# 28Pins_Schematic.net
KiCad netlist of a schematic drawn in Altium Designer
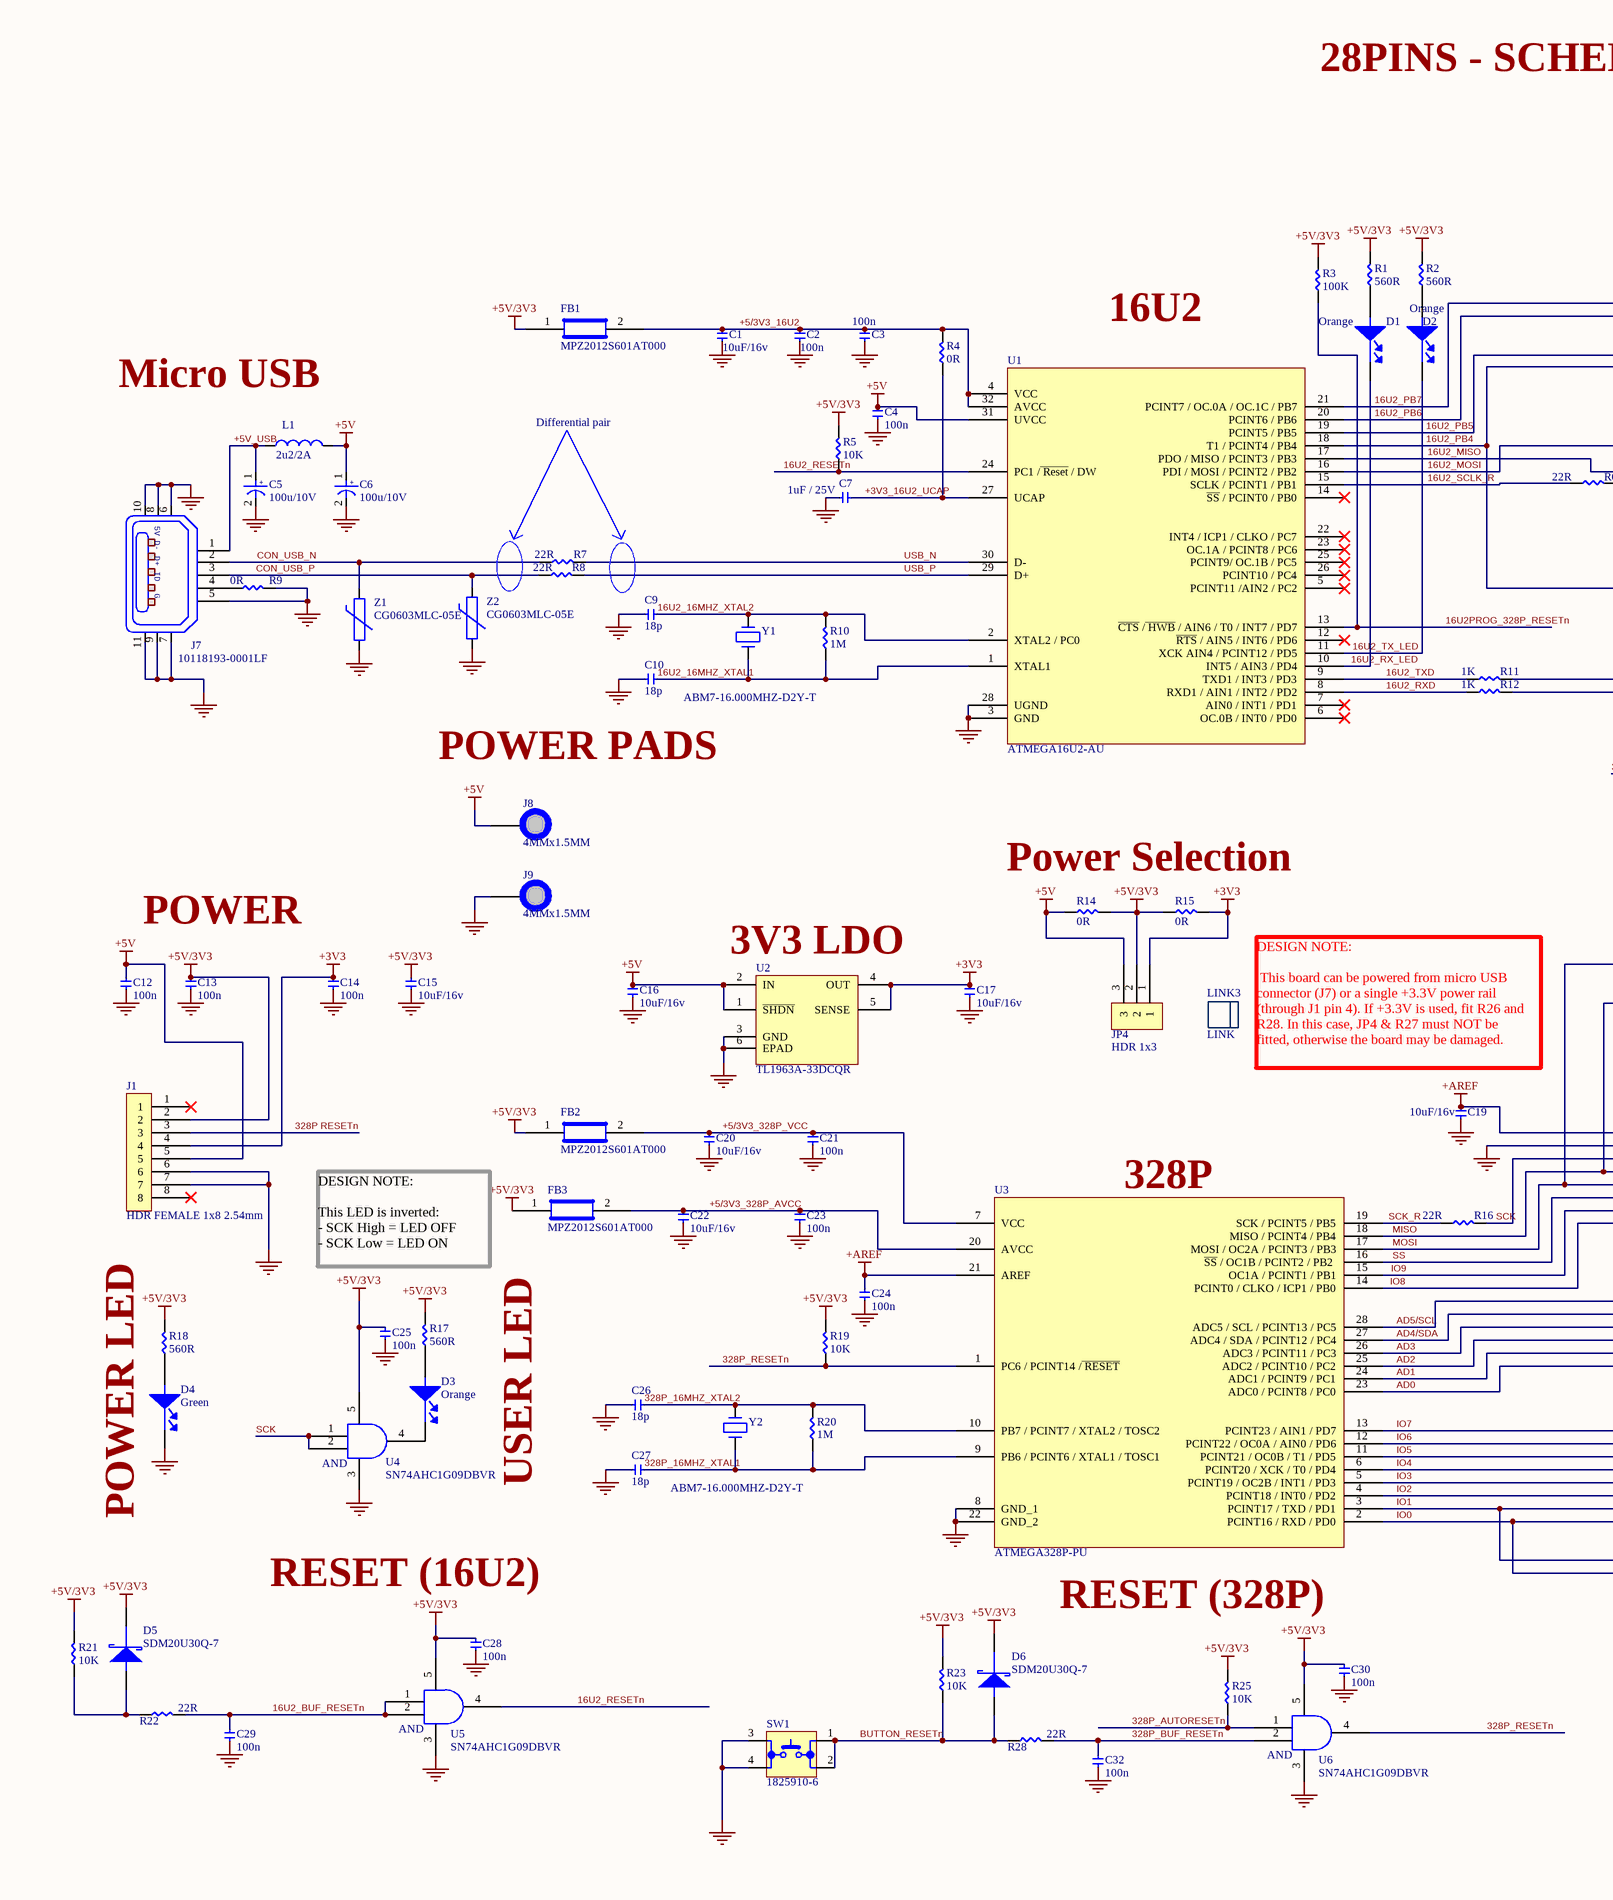
[diagram p0: 28Pins_Schematic.SchDoc, left]
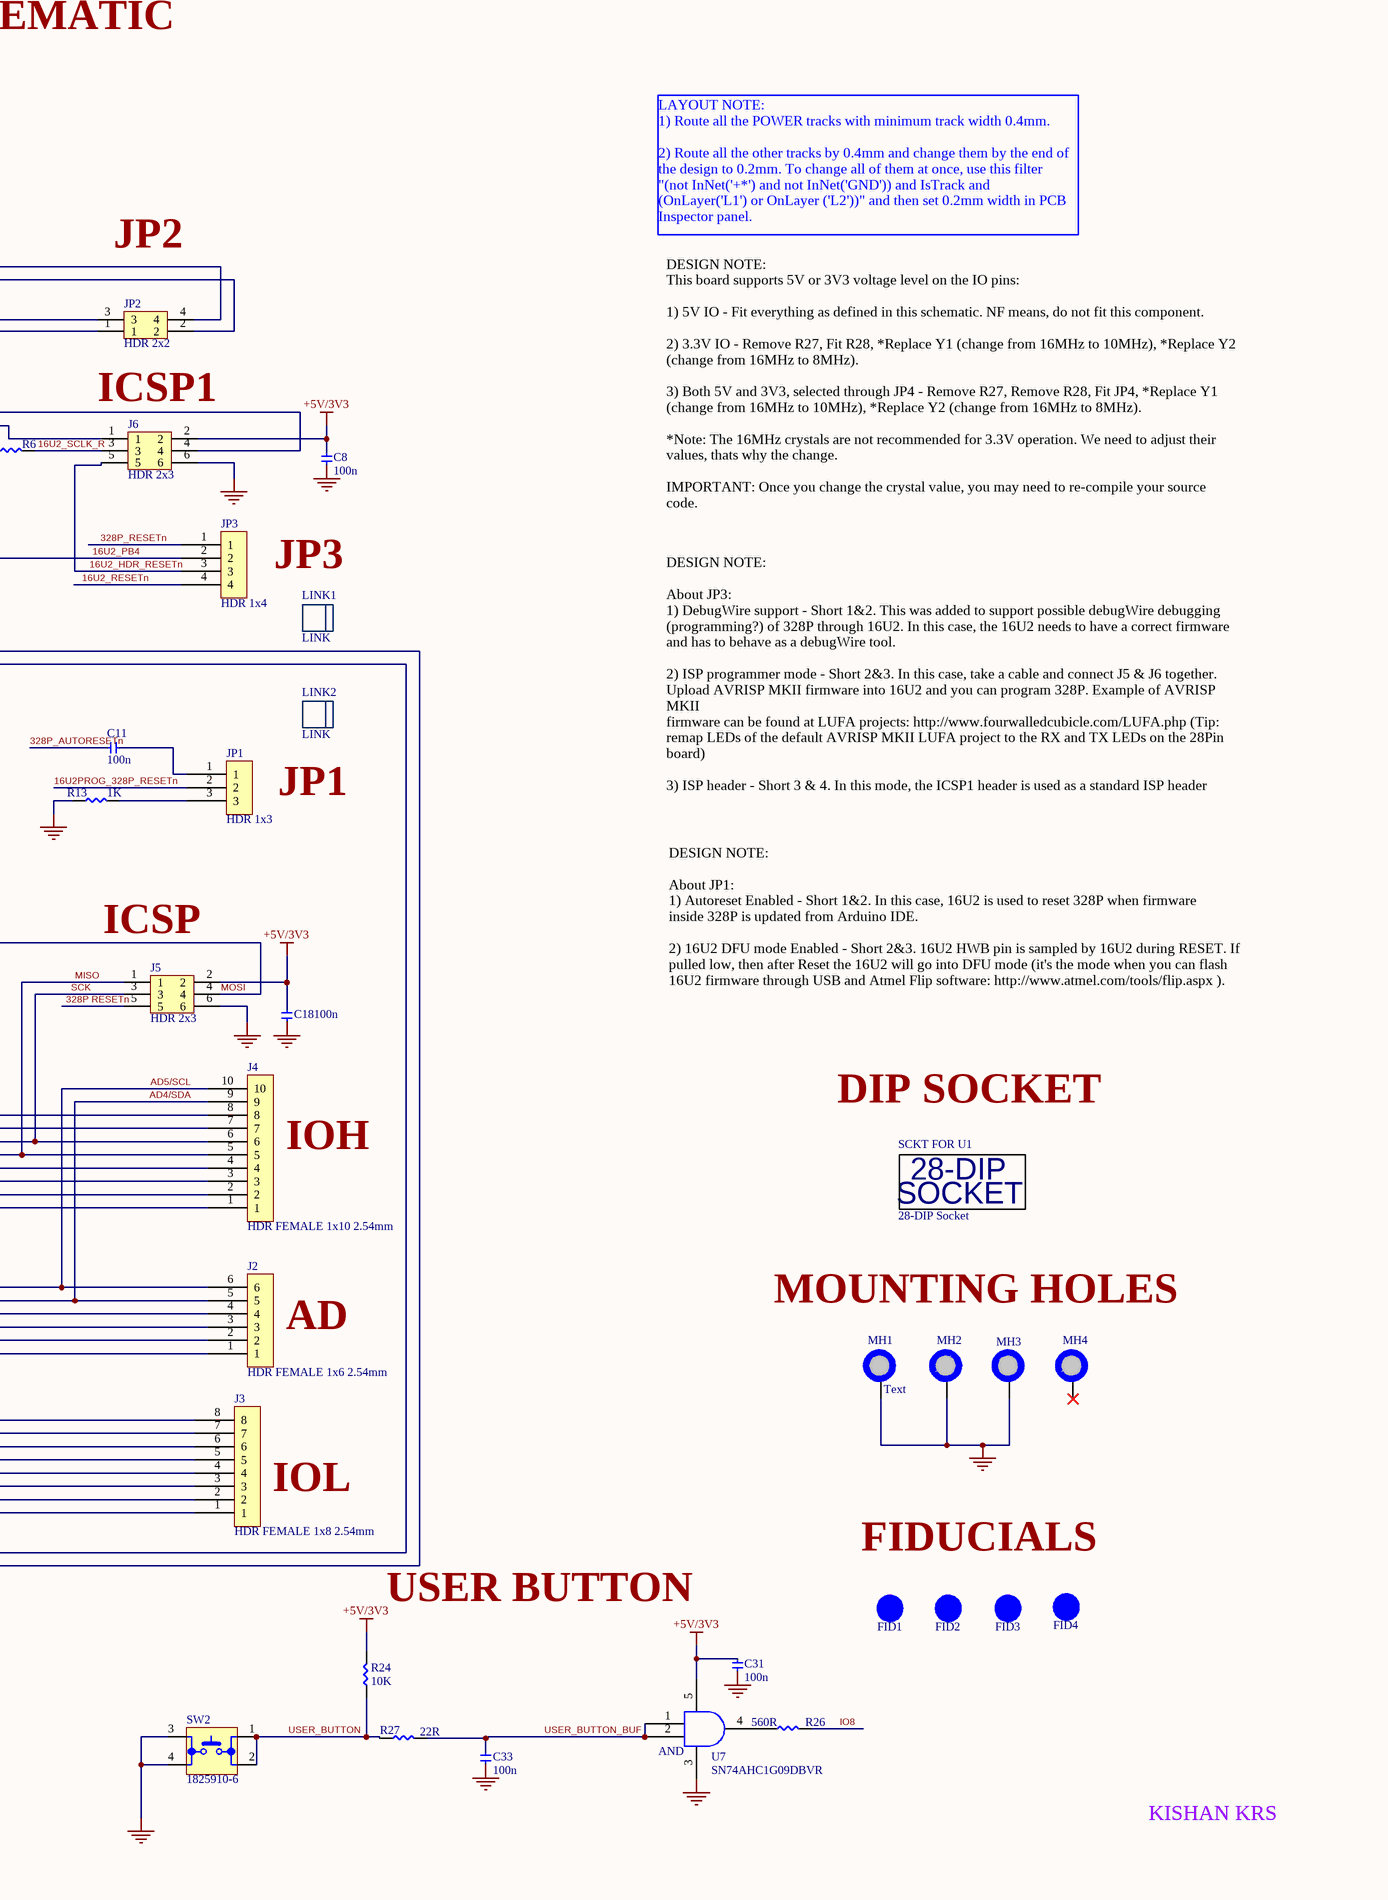
[diagram p1: 28Pins_Schematic.SchDoc, right]

(export (version "E")
  (design (tool "Eeschema 10.0.6"))
  (components
    (comp (ref "C1")
      (value "10uF/16v")
      (footprint "C0805")
      (fields
        (field (name "MANUFACTURER") "TDK")
        (field (name "MANUFACTURER PART NUMBER") "CGA4J1X5R1C106K125AC")
        (field (name "TOLERANCE") "10%")
      )
      (libsource (lib "28Pins_Project_V1I1") (part "CGA4J1X5R1C106K125AC"))
    )
    (comp (ref "C2")
      (value "100n")
      (footprint "C0805")
      (description "C Series 0805 0.1 uF 50 V ±10 % Tolerance X7R SMT Multilayer Ceramic Capacitor")
      (fields
        (field (name "MANUFACTURER") "TDK")
        (field (name "MANUFACTURER PART NUMBER") "C2012X7R1H104K085AA")
      )
      (libsource (lib "28Pins_Project_V1I1") (part "C2012X7R1H104K085AA"))
    )
    (comp (ref "C3")
      (value "100n")
      (footprint "C0805")
      (description "C Series 0805 0.1 uF 50 V ±10 % Tolerance X7R SMT Multilayer Ceramic Capacitor")
      (fields
        (field (name "MANUFACTURER") "TDK")
        (field (name "MANUFACTURER PART NUMBER") "C2012X7R1H104K085AA")
      )
      (libsource (lib "28Pins_Project_V1I1") (part "C2012X7R1H104K085AA"))
    )
    (comp (ref "C4")
      (value "100n")
      (footprint "C0805")
      (description "C Series 0805 0.1 uF 50 V ±10 % Tolerance X7R SMT Multilayer Ceramic Capacitor")
      (fields
        (field (name "MANUFACTURER") "TDK")
        (field (name "MANUFACTURER PART NUMBER") "C2012X7R1H104K085AA")
      )
      (libsource (lib "28Pins_Project_V1I1") (part "C2012X7R1H104K085AA"))
    )
    (comp (ref "C5")
      (value "100u/10V")
      (footprint "C_ALU_C_SIZE")
      (description "CAP ALUM 100UF 20% 10V SMD")
      (fields
        (field (name "MANUFACTURER") "Panasonic")
        (field (name "MANUFACTURER PART NUMBER") "EEE-1AA101WR")
      )
      (libsource (lib "28Pins_Project_V1I1") (part "EEE-1AA101WR"))
    )
    (comp (ref "C6")
      (value "100u/10V")
      (footprint "C_ALU_C_SIZE")
      (description "CAP ALUM 100UF 20% 10V SMD")
      (fields
        (field (name "MANUFACTURER") "Panasonic")
        (field (name "MANUFACTURER PART NUMBER") "EEE-1AA101WR")
      )
      (libsource (lib "28Pins_Project_V1I1") (part "EEE-1AA101WR"))
    )
    (comp (ref "C7")
      (value "1uF / 25V")
      (footprint "C0805")
      (fields
        (field (name "MANUFACTURER") "TDK")
        (field (name "MANUFACTURER PART NUMBER") "C2012X5R1E105K125AA")
        (field (name "TOLERANCE") "10%")
      )
      (libsource (lib "28Pins_Project_V1I1") (part "C2012X5R1E105K125AA"))
    )
    (comp (ref "C8")
      (value "100n")
      (footprint "C0805")
      (description "C Series 0805 0.1 uF 50 V ±10 % Tolerance X7R SMT Multilayer Ceramic Capacitor")
      (fields
        (field (name "MANUFACTURER") "TDK")
        (field (name "MANUFACTURER PART NUMBER") "C2012X7R1H104K085AA")
      )
      (libsource (lib "28Pins_Project_V1I1") (part "C2012X7R1H104K085AA"))
    )
    (comp (ref "C9")
      (value "18p")
      (footprint "C0805")
      (description "Cap Ceramic 18pF 50V C0G 5% SMD 0805 125C Paper T/R")
      (fields
        (field (name "MANUFACTURER") "KEMET")
        (field (name "MANUFACTURER PART NUMBER") "C0805C180J5GACTU")
      )
      (libsource (lib "28Pins_Project_V1I1") (part "C0805C180J5GACTU"))
    )
    (comp (ref "C10")
      (value "18p")
      (footprint "C0805")
      (description "Cap Ceramic 18pF 50V C0G 5% SMD 0805 125C Paper T/R")
      (fields
        (field (name "MANUFACTURER") "KEMET")
        (field (name "MANUFACTURER PART NUMBER") "C0805C180J5GACTU")
      )
      (libsource (lib "28Pins_Project_V1I1") (part "C0805C180J5GACTU"))
    )
    (comp (ref "C11")
      (value "100n")
      (footprint "C0805")
      (description "C Series 0805 0.1 uF 50 V ±10 % Tolerance X7R SMT Multilayer Ceramic Capacitor")
      (fields
        (field (name "MANUFACTURER") "TDK")
        (field (name "MANUFACTURER PART NUMBER") "C2012X7R1H104K085AA")
      )
      (libsource (lib "28Pins_Project_V1I1") (part "C2012X7R1H104K085AA"))
    )
    (comp (ref "C12")
      (value "100n")
      (footprint "C0805")
      (description "C Series 0805 0.1 uF 50 V ±10 % Tolerance X7R SMT Multilayer Ceramic Capacitor")
      (fields
        (field (name "MANUFACTURER") "TDK")
        (field (name "MANUFACTURER PART NUMBER") "C2012X7R1H104K085AA")
      )
      (libsource (lib "28Pins_Project_V1I1") (part "C2012X7R1H104K085AA"))
    )
    (comp (ref "C13")
      (value "100n")
      (footprint "C0805")
      (description "C Series 0805 0.1 uF 50 V ±10 % Tolerance X7R SMT Multilayer Ceramic Capacitor")
      (fields
        (field (name "MANUFACTURER") "TDK")
        (field (name "MANUFACTURER PART NUMBER") "C2012X7R1H104K085AA")
      )
      (libsource (lib "28Pins_Project_V1I1") (part "C2012X7R1H104K085AA"))
    )
    (comp (ref "C14")
      (value "100n")
      (footprint "C0805")
      (description "C Series 0805 0.1 uF 50 V ±10 % Tolerance X7R SMT Multilayer Ceramic Capacitor")
      (fields
        (field (name "MANUFACTURER") "TDK")
        (field (name "MANUFACTURER PART NUMBER") "C2012X7R1H104K085AA")
      )
      (libsource (lib "28Pins_Project_V1I1") (part "C2012X7R1H104K085AA"))
    )
    (comp (ref "C15")
      (value "10uF/16v")
      (footprint "C0805")
      (fields
        (field (name "MANUFACTURER") "TDK")
        (field (name "MANUFACTURER PART NUMBER") "CGA4J1X5R1C106K125AC")
        (field (name "TOLERANCE") "10%")
      )
      (libsource (lib "28Pins_Project_V1I1") (part "CGA4J1X5R1C106K125AC"))
    )
    (comp (ref "C16")
      (value "10uF/16v")
      (footprint "C0805")
      (fields
        (field (name "MANUFACTURER") "TDK")
        (field (name "MANUFACTURER PART NUMBER") "CGA4J1X5R1C106K125AC")
        (field (name "TOLERANCE") "10%")
      )
      (libsource (lib "28Pins_Project_V1I1") (part "CGA4J1X5R1C106K125AC"))
    )
    (comp (ref "C17")
      (value "10uF/16v")
      (footprint "C0805")
      (fields
        (field (name "MANUFACTURER") "TDK")
        (field (name "MANUFACTURER PART NUMBER") "CGA4J1X5R1C106K125AC")
        (field (name "TOLERANCE") "10%")
      )
      (libsource (lib "28Pins_Project_V1I1") (part "CGA4J1X5R1C106K125AC"))
    )
    (comp (ref "C18")
      (value "100n")
      (footprint "C0805")
      (description "C Series 0805 0.1 uF 50 V ±10 % Tolerance X7R SMT Multilayer Ceramic Capacitor")
      (fields
        (field (name "MANUFACTURER") "TDK")
        (field (name "MANUFACTURER PART NUMBER") "C2012X7R1H104K085AA")
      )
      (libsource (lib "28Pins_Project_V1I1") (part "C2012X7R1H104K085AA"))
    )
    (comp (ref "C19")
      (value "10uF/16v")
      (footprint "C0805")
      (fields
        (field (name "MANUFACTURER") "TDK")
        (field (name "MANUFACTURER PART NUMBER") "CGA4J1X5R1C106K125AC")
        (field (name "TOLERANCE") "10%")
      )
      (libsource (lib "28Pins_Project_V1I1") (part "CGA4J1X5R1C106K125AC"))
    )
    (comp (ref "C20")
      (value "10uF/16v")
      (footprint "C0805")
      (fields
        (field (name "MANUFACTURER") "TDK")
        (field (name "MANUFACTURER PART NUMBER") "CGA4J1X5R1C106K125AC")
        (field (name "TOLERANCE") "10%")
      )
      (libsource (lib "28Pins_Project_V1I1") (part "CGA4J1X5R1C106K125AC"))
    )
    (comp (ref "C21")
      (value "100n")
      (footprint "C0805")
      (description "C Series 0805 0.1 uF 50 V ±10 % Tolerance X7R SMT Multilayer Ceramic Capacitor")
      (fields
        (field (name "MANUFACTURER") "TDK")
        (field (name "MANUFACTURER PART NUMBER") "C2012X7R1H104K085AA")
      )
      (libsource (lib "28Pins_Project_V1I1") (part "C2012X7R1H104K085AA"))
    )
    (comp (ref "C22")
      (value "10uF/16v")
      (footprint "C0805")
      (fields
        (field (name "MANUFACTURER") "TDK")
        (field (name "MANUFACTURER PART NUMBER") "CGA4J1X5R1C106K125AC")
        (field (name "TOLERANCE") "10%")
      )
      (libsource (lib "28Pins_Project_V1I1") (part "CGA4J1X5R1C106K125AC"))
    )
    (comp (ref "C23")
      (value "100n")
      (footprint "C0805")
      (description "C Series 0805 0.1 uF 50 V ±10 % Tolerance X7R SMT Multilayer Ceramic Capacitor")
      (fields
        (field (name "MANUFACTURER") "TDK")
        (field (name "MANUFACTURER PART NUMBER") "C2012X7R1H104K085AA")
      )
      (libsource (lib "28Pins_Project_V1I1") (part "C2012X7R1H104K085AA"))
    )
    (comp (ref "C24")
      (value "100n")
      (footprint "C0805")
      (description "C Series 0805 0.1 uF 50 V ±10 % Tolerance X7R SMT Multilayer Ceramic Capacitor")
      (fields
        (field (name "MANUFACTURER") "TDK")
        (field (name "MANUFACTURER PART NUMBER") "C2012X7R1H104K085AA")
      )
      (libsource (lib "28Pins_Project_V1I1") (part "C2012X7R1H104K085AA"))
    )
    (comp (ref "C25")
      (value "100n")
      (footprint "C0805")
      (description "C Series 0805 0.1 uF 50 V ±10 % Tolerance X7R SMT Multilayer Ceramic Capacitor")
      (fields
        (field (name "MANUFACTURER") "TDK")
        (field (name "MANUFACTURER PART NUMBER") "C2012X7R1H104K085AA")
      )
      (libsource (lib "28Pins_Project_V1I1") (part "C2012X7R1H104K085AA"))
    )
    (comp (ref "C26")
      (value "18p")
      (footprint "C0805")
      (description "Cap Ceramic 18pF 50V C0G 5% SMD 0805 125C Paper T/R")
      (fields
        (field (name "MANUFACTURER") "KEMET")
        (field (name "MANUFACTURER PART NUMBER") "C0805C180J5GACTU")
      )
      (libsource (lib "28Pins_Project_V1I1") (part "C0805C180J5GACTU"))
    )
    (comp (ref "C27")
      (value "18p")
      (footprint "C0805")
      (description "Cap Ceramic 18pF 50V C0G 5% SMD 0805 125C Paper T/R")
      (fields
        (field (name "MANUFACTURER") "KEMET")
        (field (name "MANUFACTURER PART NUMBER") "C0805C180J5GACTU")
      )
      (libsource (lib "28Pins_Project_V1I1") (part "C0805C180J5GACTU"))
    )
    (comp (ref "C28")
      (value "100n")
      (footprint "C0805")
      (description "C Series 0805 0.1 uF 50 V ±10 % Tolerance X7R SMT Multilayer Ceramic Capacitor")
      (fields
        (field (name "MANUFACTURER") "TDK")
        (field (name "MANUFACTURER PART NUMBER") "C2012X7R1H104K085AA")
      )
      (libsource (lib "28Pins_Project_V1I1") (part "C2012X7R1H104K085AA"))
    )
    (comp (ref "C29")
      (value "100n")
      (footprint "C0805")
      (description "C Series 0805 0.1 uF 50 V ±10 % Tolerance X7R SMT Multilayer Ceramic Capacitor")
      (fields
        (field (name "MANUFACTURER") "TDK")
        (field (name "MANUFACTURER PART NUMBER") "C2012X7R1H104K085AA")
      )
      (libsource (lib "28Pins_Project_V1I1") (part "C2012X7R1H104K085AA"))
    )
    (comp (ref "C30")
      (value "100n")
      (footprint "C0805")
      (description "C Series 0805 0.1 uF 50 V ±10 % Tolerance X7R SMT Multilayer Ceramic Capacitor")
      (fields
        (field (name "MANUFACTURER") "TDK")
        (field (name "MANUFACTURER PART NUMBER") "C2012X7R1H104K085AA")
      )
      (libsource (lib "28Pins_Project_V1I1") (part "C2012X7R1H104K085AA"))
    )
    (comp (ref "C31")
      (value "100n")
      (footprint "C0805")
      (description "C Series 0805 0.1 uF 50 V ±10 % Tolerance X7R SMT Multilayer Ceramic Capacitor")
      (fields
        (field (name "MANUFACTURER") "TDK")
        (field (name "MANUFACTURER PART NUMBER") "C2012X7R1H104K085AA")
      )
      (libsource (lib "28Pins_Project_V1I1") (part "C2012X7R1H104K085AA"))
    )
    (comp (ref "C32")
      (value "100n")
      (footprint "C0805")
      (description "C Series 0805 0.1 uF 50 V ±10 % Tolerance X7R SMT Multilayer Ceramic Capacitor")
      (fields
        (field (name "MANUFACTURER") "TDK")
        (field (name "MANUFACTURER PART NUMBER") "C2012X7R1H104K085AA")
      )
      (libsource (lib "28Pins_Project_V1I1") (part "C2012X7R1H104K085AA"))
    )
    (comp (ref "C33")
      (value "100n")
      (footprint "C0805")
      (description "C Series 0805 0.1 uF 50 V ±10 % Tolerance X7R SMT Multilayer Ceramic Capacitor")
      (fields
        (field (name "MANUFACTURER") "TDK")
        (field (name "MANUFACTURER PART NUMBER") "C2012X7R1H104K085AA")
      )
      (libsource (lib "28Pins_Project_V1I1") (part "C2012X7R1H104K085AA"))
    )
    (comp (ref "D1")
      (value "Orange")
      (footprint "LED_0603")
      (description "Smartled Orange Lc")
      (fields
        (field (name "MANUFACTURER") "Osram Opto")
        (field (name "MANUFACTURER PART NUMBER") "LOL29K-H2K1-24-Z")
      )
      (libsource (lib "28Pins_Project_V1I1") (part "LOL29K-H2K1-24-Z"))
    )
    (comp (ref "D2")
      (value "Orange")
      (footprint "LED_0603")
      (description "Smartled Orange Lc")
      (fields
        (field (name "MANUFACTURER") "Osram Opto")
        (field (name "MANUFACTURER PART NUMBER") "LOL29K-H2K1-24-Z")
      )
      (libsource (lib "28Pins_Project_V1I1") (part "LOL29K-H2K1-24-Z"))
    )
    (comp (ref "D3")
      (value "Orange")
      (footprint "LED_0603")
      (description "Smartled Orange Lc")
      (fields
        (field (name "MANUFACTURER") "Osram Opto")
        (field (name "MANUFACTURER PART NUMBER") "LOL29K-H2K1-24-Z")
      )
      (libsource (lib "28Pins_Project_V1I1") (part "LOL29K-H2K1-24-Z"))
    )
    (comp (ref "D4")
      (value "Green")
      (footprint "LED_0603")
      (description "Green 574nm LED Indication - Discrete 1.9V 0603 (1608 Metric)")
      (fields (field (name "MANUFACTURER") "Bivar") (field (name "MANUFACTURER PART NUMBER") "SM0603GCL"))
      (libsource (lib "28Pins_Project_V1I1") (part "SM0603GCL"))
    )
    (comp (ref "D5")
      (value "SDM20U30Q-7")
      (footprint "SOD523")
      (description "Schottky Rectifier, 30V, 0.2A, Sod-523 Rohs Compliant: Yes")
      (fields (field (name "MANUFACTURER") "Diodes"))
      (libsource (lib "28Pins_Project_V1I1") (part "SDM20U30Q-7"))
    )
    (comp (ref "D6")
      (value "SDM20U30Q-7")
      (footprint "SOD523")
      (description "Schottky Rectifier, 30V, 0.2A, Sod-523 Rohs Compliant: Yes")
      (fields (field (name "MANUFACTURER") "Diodes"))
      (libsource (lib "28Pins_Project_V1I1") (part "SDM20U30Q-7"))
    )
    (comp (ref "FB1")
      (value "MPZ2012S601AT000")
      (footprint "C0805")
      (description "0805 600Ω ±25% DCR=0.1Ω 2A")
      (fields (field (name "MANUFACTURER") "TDK"))
      (libsource (lib "28Pins_Project_V1I1") (part "MPZ2012S601AT000"))
    )
    (comp (ref "FB2")
      (value "MPZ2012S601AT000")
      (footprint "C0805")
      (description "0805 600Ω ±25% DCR=0.1Ω 2A")
      (fields (field (name "MANUFACTURER") "TDK"))
      (libsource (lib "28Pins_Project_V1I1") (part "MPZ2012S601AT000"))
    )
    (comp (ref "FB3")
      (value "MPZ2012S601AT000")
      (footprint "C0805")
      (description "0805 600Ω ±25% DCR=0.1Ω 2A")
      (fields (field (name "MANUFACTURER") "TDK"))
      (libsource (lib "28Pins_Project_V1I1") (part "MPZ2012S601AT000"))
    )
    (comp (ref "FID1")
      (value "FID_1MMC")
      (footprint "FID_40x120D")
      (description "Fiducial 40mil Diameter, 120mil Mask")
      (libsource (lib "28Pins_Project_V1I1") (part "FID_1MMC"))
    )
    (comp (ref "FID2")
      (value "FID_1MMC")
      (footprint "FID_40x120D")
      (description "Fiducial 40mil Diameter, 120mil Mask")
      (libsource (lib "28Pins_Project_V1I1") (part "FID_1MMC"))
    )
    (comp (ref "FID3")
      (value "FID_1MMC")
      (footprint "FID_40x120D")
      (description "Fiducial 40mil Diameter, 120mil Mask")
      (libsource (lib "28Pins_Project_V1I1") (part "FID_1MMC"))
    )
    (comp (ref "FID4")
      (value "FID_1MMC")
      (footprint "FID_40x120D")
      (description "Fiducial 40mil Diameter, 120mil Mask")
      (libsource (lib "28Pins_Project_V1I1") (part "FID_1MMC"))
    )
    (comp (ref "J1")
      (value "HDR FEMALE 1x8 2.54mm")
      (footprint "Hdr_Female_1x8_2.54mm")
      (description "2.54mm (0.1\") Pitch SIL Vertical PC Tail Socket Assembly, selective gold + tin, 8 contacts")
      (fields (field (name "MANUFACTURER") "Harwin") (field (name "MANUFACTURER PART NUMBER") "M20-7820842"))
      (libsource (lib "") (part "M20-7820842_1"))
    )
    (comp (ref "J2")
      (value "HDR FEMALE 1x6 2.54mm")
      (footprint "Hdr_Female_1x6_2.54mm")
      (description "2.54mm (0.1\") Pitch SIL Vertical PC Tail Socket Assembly, tin, 6 contacts")
      (fields (field (name "MANUFACTURER") "Harwin") (field (name "MANUFACTURER PART NUMBER") "M20-7820646"))
      (libsource (lib "28Pins_Project_V1I1") (part "M20-7820646"))
    )
    (comp (ref "J3")
      (value "HDR FEMALE 1x8 2.54mm")
      (footprint "Hdr_Female_1x8_2.54mm")
      (description "2.54mm (0.1\") Pitch SIL Vertical PC Tail Socket Assembly, selective gold + tin, 8 contacts")
      (fields (field (name "MANUFACTURER") "Harwin") (field (name "MANUFACTURER PART NUMBER") "M20-7820842"))
      (libsource (lib "28Pins_Project_V1I1") (part "M20-7820842"))
    )
    (comp (ref "J4")
      (value "HDR FEMALE 1x10 2.54mm")
      (footprint "Hdr_Female_1x10_2.54mm")
      (description "2.54mm (0.1\") Pitch SIL Vertical PC Tail Socket Assembly, tin, 10 contacts")
      (fields (field (name "MANUFACTURER") "Harwin") (field (name "MANUFACTURER PART NUMBER") "M20-7821046"))
      (libsource (lib "28Pins_Project_V1I1") (part "M20-7821046"))
    )
    (comp (ref "J5")
      (value "HDR 2x3")
      (footprint "HDR_2x3_2.54MM")
      (description "2 Row 6 Position 2.54 mm Straight Unshrouded Male Pin Header")
      (fields
        (field (name "MANUFACTURER") "Amphenol Communications Solutions")
        (field (name "MANUFACTURER PART NUMBER") "67997-206HLF")
      )
      (libsource (lib "28Pins_Project_V1I1") (part "67997-206HLF"))
    )
    (comp (ref "J6")
      (value "HDR 2x3")
      (footprint "HDR_2x3_2.54MM")
      (description "2 Row 6 Position 2.54 mm Straight Unshrouded Male Pin Header")
      (fields
        (field (name "MANUFACTURER") "Amphenol Communications Solutions")
        (field (name "MANUFACTURER PART NUMBER") "67997-206HLF")
      )
      (libsource (lib "28Pins_Project_V1I1") (part "67997-206HLF"))
    )
    (comp (ref "J7")
      (value "10118193-0001LF")
      (footprint "10118193")
      (description "FCI Right Angle Surface Mount Mount Female USB Connector; 100 V ac; 1.8A")
      (fields (field (name "MANUFACTURER") "Amphenol ICC / FCI"))
      (libsource (lib "28Pins_Project_V1I1") (part "10118193-0001LF"))
    )
    (comp (ref "J8")
      (value "4MMx1.5MM")
      (footprint "PAD_WITH_HOLE_4MMx1.5MM")
      (description "pad with a hole 4mm x 1.5 mm")
      (libsource (lib "28Pins_Project_V1I1") (part "PAD_WITH_HOLE_4MMx1.5MM"))
    )
    (comp (ref "J9")
      (value "4MMx1.5MM")
      (footprint "PAD_WITH_HOLE_4MMx1.5MM")
      (description "pad with a hole 4mm x 1.5 mm")
      (libsource (lib "28Pins_Project_V1I1") (part "PAD_WITH_HOLE_4MMx1.5MM"))
    )
    (comp (ref "JP1")
      (value "HDR 1x3")
      (footprint "Hdr_1x3_2.54mm")
      (description "Conn Unshrouded Header HDR 3 POS 2.54mm Solder ST Top Entry Thru-Hole BergStik® Automotive Bulk")
      (fields
        (field (name "MANUFACTURER") "Amphenol ICC / FCI")
        (field (name "MANUFACTURER PART NUMBER") "68000-103HLF")
      )
      (libsource (lib "28Pins_Project_V1I1") (part "68000-103HLF"))
    )
    (comp (ref "JP2")
      (value "HDR 2x2")
      (footprint "HDR_2x2_2.54MM")
      (description "Conn Unshrouded Header HDR 4 POS 2.54mm Solder ST Thru-Hole Poly Bag")
      (fields
        (field (name "MANUFACTURER") "Amphenol ICC / FCI")
        (field (name "MANUFACTURER PART NUMBER") "68491-104HLF")
      )
      (libsource (lib "28Pins_Project_V1I1") (part "68491-104HLF"))
    )
    (comp (ref "JP3")
      (value "HDR 1x4")
      (footprint "HDR_1x4_2.54mm")
      (description "Conn Unshrouded Header HDR 4 POS 2.54mm Solder ST Thru-Hole Bag")
      (fields
        (field (name "MANUFACTURER") "Amphenol ICC / FCI")
        (field (name "MANUFACTURER PART NUMBER") "68001-204HLF")
      )
      (libsource (lib "28Pins_Project_V1I1") (part "68001-204HLF"))
    )
    (comp (ref "JP4")
      (value "HDR 1x3")
      (footprint "Hdr_1x3_2.54mm")
      (description "Conn Unshrouded Header HDR 3 POS 2.54mm Solder ST Top Entry Thru-Hole BergStik® Automotive Bulk")
      (fields
        (field (name "MANUFACTURER") "Amphenol ICC / FCI")
        (field (name "MANUFACTURER PART NUMBER") "68000-103HLF")
      )
      (libsource (lib "") (part "68000-103HLF_1"))
    )
    (comp (ref "L1")
      (value "2u2/2A")
      (footprint "C1210_IND")
      (description "Inductor RF Chip Wirewound 2.2uH 20% 100KHz 1.13A 0.104Ohm DCR 1210 T/R")
      (fields
        (field (name "MANUFACTURER") "KEMET")
        (field (name "MANUFACTURER PART NUMBER") "L1210R2R2MDWIT")
      )
      (libsource (lib "28Pins_Project_V1I1") (part "L1210R2R2MDWIT"))
    )
    (comp (ref "LINK1")
      (value "LINK")
      (description "2 Position 2.54 mm Centerline Single Circuit Open Top Jumper")
      (fields
        (field (name "MANUFACTURER") "Sullins")
        (field (name "MANUFACTURER PART NUMBER") "QPC02SXGN-RC")
      )
      (libsource (lib "28Pins_Project_V1I1") (part "QPC02SXGN-RC"))
    )
    (comp (ref "LINK2")
      (value "LINK")
      (description "2 Position 2.54 mm Centerline Single Circuit Open Top Jumper")
      (fields
        (field (name "MANUFACTURER") "Sullins")
        (field (name "MANUFACTURER PART NUMBER") "QPC02SXGN-RC")
      )
      (libsource (lib "28Pins_Project_V1I1") (part "QPC02SXGN-RC"))
    )
    (comp (ref "LINK3")
      (value "LINK")
      (description "2 Position 2.54 mm Centerline Single Circuit Open Top Jumper")
      (fields
        (field (name "MANUFACTURER") "Sullins")
        (field (name "MANUFACTURER PART NUMBER") "QPC02SXGN-RC")
      )
      (libsource (lib "28Pins_Project_V1I1") (part "QPC02SXGN-RC"))
    )
    (comp (ref "MH1")
      (value "MH_7.4MMC_3.2MMD")
      (footprint "MH_7.4MMD_3.2MMD")
      (description "Mounting Hole 7.4mm Diameter, 3.2mm Drill")
      (libsource (lib "28Pins_Project_V1I1") (part "MH_7.4MMC_3.2MMD"))
    )
    (comp (ref "MH2")
      (value "MH_7.4MMC_3.2MMD")
      (footprint "MH_7.4MMD_3.2MMD")
      (description "Mounting Hole 7.4mm Diameter, 3.2mm Drill")
      (libsource (lib "28Pins_Project_V1I1") (part "MH_7.4MMC_3.2MMD"))
    )
    (comp (ref "MH3")
      (value "MH_7.4MMC_3.2MMD")
      (footprint "MH_7.4MMD_3.2MMD")
      (description "Mounting Hole 7.4mm Diameter, 3.2mm Drill")
      (libsource (lib "28Pins_Project_V1I1") (part "MH_7.4MMC_3.2MMD"))
    )
    (comp (ref "MH4")
      (value "MH_7.4MMNC_3.2MMD")
      (footprint "MH_7.4MMNC_3.2MMD_NON_COPPER_NPTH")
      (description "Hole 7.4mm Diameter(Non Copper), 3.2mm Drill NPTH")
      (libsource (lib "28Pins_Project_V1I1") (part "MH_7.4MMNC_3.2MMD"))
    )
    (comp (ref "R1")
      (value "560R")
      (footprint "R0805")
      (description "Res General Purpose Thick Film 0805 560 Ohm 1% 1/8W ±100ppm/°C Molded Paper T/R")
      (fields
        (field (name "MANUFACTURER") "Yageo")
        (field (name "MANUFACTURER PART NUMBER") "RC0805FR-07560RL")
      )
      (libsource (lib "28Pins_Project_V1I1") (part "RC0805FR-07560RL"))
    )
    (comp (ref "R2")
      (value "560R")
      (footprint "R0805")
      (description "Res General Purpose Thick Film 0805 560 Ohm 1% 1/8W ±100ppm/°C Molded Paper T/R")
      (fields
        (field (name "MANUFACTURER") "Yageo")
        (field (name "MANUFACTURER PART NUMBER") "RC0805FR-07560RL")
      )
      (libsource (lib "28Pins_Project_V1I1") (part "RC0805FR-07560RL"))
    )
    (comp (ref "R3")
      (value "100K")
      (footprint "R0805")
      (description "Res Thick Film 0805 100K Ohm 1% 1/8W ±100ppm/°C Molded SMD Paper T/R")
      (fields
        (field (name "MANUFACTURER") "Yageo")
        (field (name "MANUFACTURER PART NUMBER") "RC0805FR-07100KL")
      )
      (libsource (lib "28Pins_Project_V1I1") (part "RC0805FR-07100KL"))
    )
    (comp (ref "R4")
      (value "0R")
      (footprint "R0805")
      (description "Surface Mount Thick Film Resistor, RC Series, 125 mW, - 5%, 150 V, 0805 [2012 Metric]")
      (fields
        (field (name "MANUFACTURER") "Yageo")
        (field (name "MANUFACTURER PART NUMBER") "RC0805JR-070RL")
      )
      (libsource (lib "28Pins_Project_V1I1") (part "RC0805JR-070RL"))
    )
    (comp (ref "R5")
      (value "10K")
      (footprint "R0805")
      (description "Res Thick Film 0805 10K Ohm 1% 0.125W(1/8W) +/-100ppm/C Epoxy Pad SMD T/R")
      (fields
        (field (name "MANUFACTURER") "Yageo")
        (field (name "MANUFACTURER PART NUMBER") "RC0805FR-0710KL")
      )
      (libsource (lib "28Pins_Project_V1I1") (part "RC0805FR-0710KL"))
    )
    (comp (ref "R6")
      (value "22R")
      (footprint "R0805")
      (description "Res Thick Film 0805 220 Ohm 1% 1/8W +/-100ppm/ßC Molded SMD Paper T/R")
      (fields
        (field (name "MANUFACTURER") "Yageo")
        (field (name "MANUFACTURER PART NUMBER") "RC0805FR-07220RL")
      )
      (libsource (lib "28Pins_Project_V1I1") (part "RC0805FR-07220RL"))
    )
    (comp (ref "R7")
      (value "22R")
      (footprint "R0805")
      (description "Res Thick Film 0805 220 Ohm 1% 1/8W +/-100ppm/ßC Molded SMD Paper T/R")
      (fields
        (field (name "MANUFACTURER") "Yageo")
        (field (name "MANUFACTURER PART NUMBER") "RC0805FR-07220RL")
      )
      (libsource (lib "28Pins_Project_V1I1") (part "RC0805FR-07220RL"))
    )
    (comp (ref "R8")
      (value "22R")
      (footprint "R0805")
      (description "Res Thick Film 0805 220 Ohm 1% 1/8W +/-100ppm/ßC Molded SMD Paper T/R")
      (fields
        (field (name "MANUFACTURER") "Yageo")
        (field (name "MANUFACTURER PART NUMBER") "RC0805FR-07220RL")
      )
      (libsource (lib "28Pins_Project_V1I1") (part "RC0805FR-07220RL"))
    )
    (comp (ref "R9")
      (value "0R")
      (footprint "R0805")
      (description "Surface Mount Thick Film Resistor, RC Series, 125 mW, - 5%, 150 V, 0805 [2012 Metric]")
      (fields
        (field (name "MANUFACTURER") "Yageo")
        (field (name "MANUFACTURER PART NUMBER") "RC0805JR-070RL")
      )
      (libsource (lib "28Pins_Project_V1I1") (part "RC0805JR-070RL"))
    )
    (comp (ref "R10")
      (value "1M")
      (footprint "R0805")
      (description "Res Thick Film 0805 1M Ohm 1% 0.125W(1/8W) ±100ppm/C Pad SMD T/R")
      (fields
        (field (name "MANUFACTURER") "Yageo Phycomp")
        (field (name "MANUFACTURER PART NUMBER") "RC0805FR-071ML")
      )
      (libsource (lib "28Pins_Project_V1I1") (part "RC0805FR-071ML"))
    )
    (comp (ref "R11")
      (value "1K")
      (footprint "R0805")
      (description "RES SMD 1K OHM 1% 1/8W 0805")
      (fields
        (field (name "MANUFACTURER") "Yageo")
        (field (name "MANUFACTURER PART NUMBER") "RC0805FR-071KL")
      )
      (libsource (lib "28Pins_Project_V1I1") (part "RC0805FR-071KL"))
    )
    (comp (ref "R12")
      (value "1K")
      (footprint "R0805")
      (description "RES SMD 1K OHM 1% 1/8W 0805")
      (fields
        (field (name "MANUFACTURER") "Yageo")
        (field (name "MANUFACTURER PART NUMBER") "RC0805FR-071KL")
      )
      (libsource (lib "28Pins_Project_V1I1") (part "RC0805FR-071KL"))
    )
    (comp (ref "R13")
      (value "1K")
      (footprint "R0805")
      (description "RES SMD 1K OHM 1% 1/8W 0805")
      (fields
        (field (name "MANUFACTURER") "Yageo")
        (field (name "MANUFACTURER PART NUMBER") "RC0805FR-071KL")
      )
      (libsource (lib "28Pins_Project_V1I1") (part "RC0805FR-071KL"))
    )
    (comp (ref "R14")
      (value "0R")
      (footprint "R0805")
      (description "Surface Mount Thick Film Resistor, RC Series, 125 mW, - 5%, 150 V, 0805 [2012 Metric]")
      (fields
        (field (name "MANUFACTURER") "Yageo")
        (field (name "MANUFACTURER PART NUMBER") "RC0805JR-070RL")
      )
      (libsource (lib "28Pins_Project_V1I1") (part "RC0805JR-070RL"))
    )
    (comp (ref "R15")
      (value "0R")
      (footprint "R0805")
      (description "Surface Mount Thick Film Resistor, RC Series, 125 mW, - 5%, 150 V, 0805 [2012 Metric]")
      (fields
        (field (name "MANUFACTURER") "Yageo")
        (field (name "MANUFACTURER PART NUMBER") "RC0805JR-070RL")
      )
      (libsource (lib "28Pins_Project_V1I1") (part "RC0805JR-070RL"))
    )
    (comp (ref "R16")
      (value "22R")
      (footprint "R0805")
      (description "Res Thick Film 0805 220 Ohm 1% 1/8W +/-100ppm/ßC Molded SMD Paper T/R")
      (fields
        (field (name "MANUFACTURER") "Yageo")
        (field (name "MANUFACTURER PART NUMBER") "RC0805FR-07220RL")
      )
      (libsource (lib "28Pins_Project_V1I1") (part "RC0805FR-07220RL"))
    )
    (comp (ref "R17")
      (value "560R")
      (footprint "R0805")
      (description "Res General Purpose Thick Film 0805 560 Ohm 1% 1/8W ±100ppm/°C Molded Paper T/R")
      (fields
        (field (name "MANUFACTURER") "Yageo")
        (field (name "MANUFACTURER PART NUMBER") "RC0805FR-07560RL")
      )
      (libsource (lib "28Pins_Project_V1I1") (part "RC0805FR-07560RL"))
    )
    (comp (ref "R18")
      (value "560R")
      (footprint "R0805")
      (description "Res General Purpose Thick Film 0805 560 Ohm 1% 1/8W ±100ppm/°C Molded Paper T/R")
      (fields
        (field (name "MANUFACTURER") "Yageo")
        (field (name "MANUFACTURER PART NUMBER") "RC0805FR-07560RL")
      )
      (libsource (lib "28Pins_Project_V1I1") (part "RC0805FR-07560RL"))
    )
    (comp (ref "R19")
      (value "10K")
      (footprint "R0805")
      (description "Res Thick Film 0805 10K Ohm 1% 0.125W(1/8W) +/-100ppm/C Epoxy Pad SMD T/R")
      (fields
        (field (name "MANUFACTURER") "Yageo")
        (field (name "MANUFACTURER PART NUMBER") "RC0805FR-0710KL")
      )
      (libsource (lib "28Pins_Project_V1I1") (part "RC0805FR-0710KL"))
    )
    (comp (ref "R20")
      (value "1M")
      (footprint "R0805")
      (description "Res Thick Film 0805 1M Ohm 1% 0.125W(1/8W) ±100ppm/C Pad SMD T/R")
      (fields
        (field (name "MANUFACTURER") "Yageo Phycomp")
        (field (name "MANUFACTURER PART NUMBER") "RC0805FR-071ML")
      )
      (libsource (lib "28Pins_Project_V1I1") (part "RC0805FR-071ML"))
    )
    (comp (ref "R21")
      (value "10K")
      (footprint "R0805")
      (description "Res Thick Film 0805 10K Ohm 1% 0.125W(1/8W) +/-100ppm/C Epoxy Pad SMD T/R")
      (fields
        (field (name "MANUFACTURER") "Yageo")
        (field (name "MANUFACTURER PART NUMBER") "RC0805FR-0710KL")
      )
      (libsource (lib "28Pins_Project_V1I1") (part "RC0805FR-0710KL"))
    )
    (comp (ref "R22")
      (value "22R")
      (footprint "R0805")
      (description "Res Thick Film 0805 220 Ohm 1% 1/8W +/-100ppm/ßC Molded SMD Paper T/R")
      (fields
        (field (name "MANUFACTURER") "Yageo")
        (field (name "MANUFACTURER PART NUMBER") "RC0805FR-07220RL")
      )
      (libsource (lib "28Pins_Project_V1I1") (part "RC0805FR-07220RL"))
    )
    (comp (ref "R23")
      (value "10K")
      (footprint "R0805")
      (description "Res Thick Film 0805 10K Ohm 1% 0.125W(1/8W) +/-100ppm/C Epoxy Pad SMD T/R")
      (fields
        (field (name "MANUFACTURER") "Yageo")
        (field (name "MANUFACTURER PART NUMBER") "RC0805FR-0710KL")
      )
      (libsource (lib "28Pins_Project_V1I1") (part "RC0805FR-0710KL"))
    )
    (comp (ref "R24")
      (value "10K")
      (footprint "R0805")
      (description "Res Thick Film 0805 10K Ohm 1% 0.125W(1/8W) +/-100ppm/C Epoxy Pad SMD T/R")
      (fields
        (field (name "MANUFACTURER") "Yageo")
        (field (name "MANUFACTURER PART NUMBER") "RC0805FR-0710KL")
      )
      (libsource (lib "28Pins_Project_V1I1") (part "RC0805FR-0710KL"))
    )
    (comp (ref "R25")
      (value "10K")
      (footprint "R0805")
      (description "Res Thick Film 0805 10K Ohm 1% 0.125W(1/8W) +/-100ppm/C Epoxy Pad SMD T/R")
      (fields
        (field (name "MANUFACTURER") "Yageo")
        (field (name "MANUFACTURER PART NUMBER") "RC0805FR-0710KL")
      )
      (libsource (lib "28Pins_Project_V1I1") (part "RC0805FR-0710KL"))
    )
    (comp (ref "R26")
      (value "560R")
      (footprint "R0805")
      (description "Res General Purpose Thick Film 0805 560 Ohm 1% 1/8W ±100ppm/°C Molded Paper T/R")
      (fields
        (field (name "MANUFACTURER") "Yageo")
        (field (name "MANUFACTURER PART NUMBER") "RC0805FR-07560RL")
      )
      (libsource (lib "28Pins_Project_V1I1") (part "RC0805FR-07560RL"))
    )
    (comp (ref "R27")
      (value "22R")
      (footprint "R0805")
      (description "Res Thick Film 0805 220 Ohm 1% 1/8W +/-100ppm/ßC Molded SMD Paper T/R")
      (fields
        (field (name "MANUFACTURER") "Yageo")
        (field (name "MANUFACTURER PART NUMBER") "RC0805FR-07220RL")
      )
      (libsource (lib "28Pins_Project_V1I1") (part "RC0805FR-07220RL"))
    )
    (comp (ref "R28")
      (value "22R")
      (footprint "R0805")
      (description "Res Thick Film 0805 220 Ohm 1% 1/8W +/-100ppm/ßC Molded SMD Paper T/R")
      (fields
        (field (name "MANUFACTURER") "Yageo")
        (field (name "MANUFACTURER PART NUMBER") "RC0805FR-07220RL")
      )
      (libsource (lib "28Pins_Project_V1I1") (part "RC0805FR-07220RL"))
    )
    (comp (ref "SCKT FOR U1")
      (value "28-DIP Socket")
      (footprint "28_DIP_7.6mm_SOCKET")
      (description "Socket DIP 28Cnts DualWipe 0.3InSpc. PhosphorBronze Nickel KinkedTail 4800Series")
      (fields (field (name "MANUFACTURER") "3M") (field (name "MANUFACTURER PART NUMBER") "4828-3004-CP"))
      (libsource (lib "28Pins_Project_V1I1") (part "4828-3004-CP"))
    )
    (comp (ref "SW1")
      (value "1825910-6")
      (footprint "1825910-6")
      (description "Switch Tactile OFF (ON) SPST Round Button PC Pins 0.05A 24VDC 1.57N Thru-Hole Loose")
      (fields (field (name "MANUFACTURER") "TE Connectivity Alcoswitch"))
      (libsource (lib "28Pins_Project_V1I1") (part "1825910-6"))
    )
    (comp (ref "SW2")
      (value "1825910-6")
      (footprint "1825910-6")
      (description "Switch Tactile OFF (ON) SPST Round Button PC Pins 0.05A 24VDC 1.57N Thru-Hole Loose")
      (fields (field (name "MANUFACTURER") "TE Connectivity Alcoswitch"))
      (libsource (lib "28Pins_Project_V1I1") (part "1825910-6"))
    )
    (comp (ref "U1")
      (value "ATMEGA16U2-AU")
      (footprint "TQFP32")
      (description "8-bit AVR MCU, 16 KB, 512 Bytes, 16 MHz, 2.7 to 5.5V, TQFP-32, RoHS")
      (fields (field (name "MANUFACTURER") "Microchip / Atmel"))
      (libsource (lib "28Pins_Project_V1I1") (part "ATMEGA16U2-AU"))
    )
    (comp (ref "U2")
      (value "TL1963A-33DCQR")
      (footprint "DCQ(R-PDSO-G6)")
      (description "LDO Regulator Pos 3.3V 1.5A 6-Pin(5+Tab) SOT-223 T/R")
      (fields (field (name "MANUFACTURER") "Texas Instruments"))
      (libsource (lib "28Pins_Project_V1I1") (part "TL1963A-33DCQR"))
    )
    (comp (ref "U3")
      (value "ATMEGA328P-PU")
      (footprint "28_DIP_7.62mm")
      (description "ATMEGA328P-PU; 8 bit Microcontroller AVR 20MHz 1; 32kb Flash; 2kb RAM; I2C SPI 2")
      (fields (field (name "MANUFACTURER") "Microchip / Atmel"))
      (libsource (lib "28Pins_Project_V1I1") (part "ATMEGA328P-PU"))
    )
    (comp (ref "U4")
      (value "SN74AHC1G09DBVR")
      (footprint "DBV_SOT_23_S")
      (description "Single 2-input, 2-V to 5.5-V AND gate with open-drain outputs 5-SOT-23 -55 to 125")
      (fields (field (name "MANUFACTURER") "Texas Instruments"))
      (libsource (lib "28Pins_Project_V1I1") (part "SN74AHC1G09DBVR"))
    )
    (comp (ref "U5")
      (value "SN74AHC1G09DBVR")
      (footprint "DBV_SOT_23_S")
      (description "Single 2-input, 2-V to 5.5-V AND gate with open-drain outputs 5-SOT-23 -55 to 125")
      (fields (field (name "MANUFACTURER") "Texas Instruments"))
      (libsource (lib "28Pins_Project_V1I1") (part "SN74AHC1G09DBVR"))
    )
    (comp (ref "U6")
      (value "SN74AHC1G09DBVR")
      (footprint "DBV_SOT_23_S")
      (description "Single 2-input, 2-V to 5.5-V AND gate with open-drain outputs 5-SOT-23 -55 to 125")
      (fields (field (name "MANUFACTURER") "Texas Instruments"))
      (libsource (lib "28Pins_Project_V1I1") (part "SN74AHC1G09DBVR"))
    )
    (comp (ref "U7")
      (value "SN74AHC1G09DBVR")
      (footprint "DBV_SOT_23_S")
      (description "Single 2-input, 2-V to 5.5-V AND gate with open-drain outputs 5-SOT-23 -55 to 125")
      (fields (field (name "MANUFACTURER") "Texas Instruments"))
      (libsource (lib "28Pins_Project_V1I1") (part "SN74AHC1G09DBVR"))
    )
    (comp (ref "Y1")
      (value "ABM7-16.000MHZ-D2Y-T")
      (footprint "ABM_v1_I1_BIG")
      (description "Crystal 16MHz ±20ppm (Tol) ±30ppm (Stability) 18pF FUND 50Ohm 2-Pin Mini-CSMD T/R")
      (fields (field (name "MANUFACTURER") "Abracon") (field (name "TOLERANCE") "20ppm"))
      (libsource (lib "28Pins_Project_V1I1") (part "ABM7-16.000MHZ-D2Y-T"))
    )
    (comp (ref "Y2")
      (value "ABM7-16.000MHZ-D2Y-T")
      (footprint "ABM_v1_I1_BIG")
      (description "Crystal 16MHz ±20ppm (Tol) ±30ppm (Stability) 18pF FUND 50Ohm 2-Pin Mini-CSMD T/R")
      (fields (field (name "MANUFACTURER") "Abracon") (field (name "TOLERANCE") "20ppm"))
      (libsource (lib "28Pins_Project_V1I1") (part "ABM7-16.000MHZ-D2Y-T"))
    )
    (comp (ref "Z1")
      (value "CG0603MLC-05E")
      (footprint "R0603")
      (description "ESD Suppressor Multilayer Varistor 5V Automotive 2-Pin Case 0603(1608Metric) T/R")
      (fields (field (name "MANUFACTURER") "Bourns") (field (name "VOLTAGE") "5V"))
      (libsource (lib "28Pins_Project_V1I1") (part "CG0603MLC-05E"))
    )
    (comp (ref "Z2")
      (value "CG0603MLC-05E")
      (footprint "R0603")
      (description "ESD Suppressor Multilayer Varistor 5V Automotive 2-Pin Case 0603(1608Metric) T/R")
      (fields (field (name "MANUFACTURER") "Bourns") (field (name "VOLTAGE") "5V"))
      (libsource (lib "28Pins_Project_V1I1") (part "CG0603MLC-05E"))
    )
  )
  (nets
    (net (code "1") (name "+3V3") (class "Default")
      (node (ref "C14") (pin "2") (pinfunction "2_2") (pintype "passive"))
      (node (ref "C17") (pin "2") (pinfunction "2_2") (pintype "passive"))
      (node (ref "J1") (pin "4") (pinfunction "4_4") (pintype "passive"))
      (node (ref "JP4") (pin "1") (pinfunction "1_1") (pintype "passive"))
      (node (ref "R15") (pin "2") (pinfunction "2_2") (pintype "passive"))
      (node (ref "U2") (pin "4") (pinfunction "OUT_4") (pintype "passive"))
      (node (ref "U2") (pin "5") (pinfunction "SENSE_5") (pintype "passive"))
    )
    (net (code "2") (name "+5V") (class "Default")
      (node (ref "C12") (pin "2") (pinfunction "2_2") (pintype "passive"))
      (node (ref "C16") (pin "2") (pinfunction "2_2") (pintype "passive"))
      (node (ref "C4") (pin "2") (pinfunction "2_2") (pintype "passive"))
      (node (ref "C6") (pin "1") (pinfunction "1_1") (pintype "passive"))
      (node (ref "J1") (pin "5") (pinfunction "5_5") (pintype "passive"))
      (node (ref "J8") (pin "1") (pinfunction "1_1") (pintype "passive"))
      (node (ref "JP4") (pin "3") (pinfunction "3_3") (pintype "passive"))
      (node (ref "L1") (pin "2") (pinfunction "2_2") (pintype "passive"))
      (node (ref "R14") (pin "1") (pinfunction "1_1") (pintype "passive"))
      (node (ref "U1") (pin "31") (pinfunction "UVCC_31") (pintype "passive"))
      (node (ref "U2") (pin "1") (pinfunction "~{SHDN}_1") (pintype "passive"))
      (node (ref "U2") (pin "2") (pinfunction "IN_2") (pintype "passive"))
    )
    (net (code "3") (name "+5V{slash}3V3") (class "Default")
      (node (ref "C13") (pin "2") (pinfunction "2_2") (pintype "passive"))
      (node (ref "C15") (pin "2") (pinfunction "2_2") (pintype "passive"))
      (node (ref "C18") (pin "2") (pinfunction "2_2") (pintype "passive"))
      (node (ref "C25") (pin "2") (pinfunction "2_2") (pintype "passive"))
      (node (ref "C28") (pin "2") (pinfunction "2_2") (pintype "passive"))
      (node (ref "C30") (pin "2") (pinfunction "2_2") (pintype "passive"))
      (node (ref "C31") (pin "2") (pinfunction "2_2") (pintype "passive"))
      (node (ref "C8") (pin "2") (pinfunction "2_2") (pintype "passive"))
      (node (ref "D5") (pin "1") (pinfunction "Cathode_1") (pintype "passive"))
      (node (ref "D6") (pin "1") (pinfunction "Cathode_1") (pintype "passive"))
      (node (ref "FB1") (pin "1") (pinfunction "1_1") (pintype "passive"))
      (node (ref "FB2") (pin "1") (pinfunction "1_1") (pintype "passive"))
      (node (ref "FB3") (pin "1") (pinfunction "1_1") (pintype "passive"))
      (node (ref "J1") (pin "2") (pinfunction "2_2") (pintype "passive"))
      (node (ref "J5") (pin "2") (pinfunction "2_2") (pintype "passive"))
      (node (ref "J6") (pin "2") (pinfunction "2_2") (pintype "passive"))
      (node (ref "JP4") (pin "2") (pinfunction "2_2") (pintype "passive"))
      (node (ref "R1") (pin "2") (pinfunction "2_2") (pintype "passive"))
      (node (ref "R14") (pin "2") (pinfunction "2_2") (pintype "passive"))
      (node (ref "R15") (pin "1") (pinfunction "1_1") (pintype "passive"))
      (node (ref "R17") (pin "2") (pinfunction "2_2") (pintype "passive"))
      (node (ref "R18") (pin "2") (pinfunction "2_2") (pintype "passive"))
      (node (ref "R19") (pin "2") (pinfunction "2_2") (pintype "passive"))
      (node (ref "R2") (pin "2") (pinfunction "2_2") (pintype "passive"))
      (node (ref "R21") (pin "2") (pinfunction "2_2") (pintype "passive"))
      (node (ref "R23") (pin "2") (pinfunction "2_2") (pintype "passive"))
      (node (ref "R24") (pin "2") (pinfunction "2_2") (pintype "passive"))
      (node (ref "R25") (pin "2") (pinfunction "2_2") (pintype "passive"))
      (node (ref "R3") (pin "2") (pinfunction "2_2") (pintype "passive"))
      (node (ref "R5") (pin "2") (pinfunction "2_2") (pintype "passive"))
      (node (ref "U4") (pin "5") (pinfunction "5_5") (pintype "passive"))
      (node (ref "U5") (pin "5") (pinfunction "5_5") (pintype "passive"))
      (node (ref "U6") (pin "5") (pinfunction "5_5") (pintype "passive"))
      (node (ref "U7") (pin "5") (pinfunction "5_5") (pintype "passive"))
    )
    (net (code "4") (name "+AREF") (class "Default")
      (node (ref "C19") (pin "2") (pinfunction "2_2") (pintype "passive"))
      (node (ref "C24") (pin "2") (pinfunction "2_2") (pintype "passive"))
      (node (ref "J4") (pin "8") (pinfunction "8_8") (pintype "passive"))
      (node (ref "U3") (pin "21") (pinfunction "AREF_21") (pintype "passive"))
    )
    (net (code "5") (name "/+3V3_16U2_UCAP") (class "Default")
      (node (ref "C7") (pin "2") (pinfunction "2_2") (pintype "passive"))
      (node (ref "R4") (pin "1") (pinfunction "1_1") (pintype "passive"))
      (node (ref "U1") (pin "27") (pinfunction "UCAP_27") (pintype "passive"))
    )
    (net (code "6") (name "/+5V_USB") (class "Default")
      (node (ref "C5") (pin "1") (pinfunction "1_1") (pintype "passive"))
      (node (ref "J7") (pin "1") (pinfunction "1_1") (pintype "passive"))
      (node (ref "L1") (pin "1") (pinfunction "1_1") (pintype "passive"))
    )
    (net (code "7") (name "/+5{slash}3V3_16U2") (class "Default")
      (node (ref "C1") (pin "2") (pinfunction "2_2") (pintype "passive"))
      (node (ref "C2") (pin "2") (pinfunction "2_2") (pintype "passive"))
      (node (ref "C3") (pin "2") (pinfunction "2_2") (pintype "passive"))
      (node (ref "FB1") (pin "2") (pinfunction "2_2") (pintype "passive"))
      (node (ref "R4") (pin "2") (pinfunction "2_2") (pintype "passive"))
      (node (ref "U1") (pin "32") (pinfunction "AVCC_32") (pintype "passive"))
      (node (ref "U1") (pin "4") (pinfunction "VCC_4") (pintype "passive"))
    )
    (net (code "8") (name "/+5{slash}3V3_328P_AVCC") (class "Default")
      (node (ref "C22") (pin "2") (pinfunction "2_2") (pintype "passive"))
      (node (ref "C23") (pin "2") (pinfunction "2_2") (pintype "passive"))
      (node (ref "FB3") (pin "2") (pinfunction "2_2") (pintype "passive"))
      (node (ref "U3") (pin "20") (pinfunction "AVCC_20") (pintype "passive"))
    )
    (net (code "9") (name "/+5{slash}3V3_328P_VCC") (class "Default")
      (node (ref "C20") (pin "2") (pinfunction "2_2") (pintype "passive"))
      (node (ref "C21") (pin "2") (pinfunction "2_2") (pintype "passive"))
      (node (ref "FB2") (pin "2") (pinfunction "2_2") (pintype "passive"))
      (node (ref "U3") (pin "7") (pinfunction "VCC_7") (pintype "passive"))
    )
    (net (code "10") (name "/16U2PROG_328P_RESETn") (class "Default")
      (node (ref "JP1") (pin "2") (pinfunction "2_2") (pintype "passive"))
      (node (ref "R3") (pin "1") (pinfunction "1_1") (pintype "passive"))
      (node (ref "U1") (pin "13") (pinfunction "~{CTS}_/~{_HWB}_/_AIN6_/_T0_/_INT7_/_PD7_13") (pintype "passive"))
    )
    (net (code "11") (name "/16U2_16MHZ_XTAL1") (class "Default")
      (node (ref "C10") (pin "2") (pinfunction "2_2") (pintype "passive"))
      (node (ref "R10") (pin "1") (pinfunction "1_1") (pintype "passive"))
      (node (ref "U1") (pin "1") (pinfunction "XTAL1_1") (pintype "passive"))
      (node (ref "Y1") (pin "1") (pinfunction "1_1") (pintype "passive"))
    )
    (net (code "12") (name "/16U2_16MHZ_XTAL2") (class "Default")
      (node (ref "C9") (pin "2") (pinfunction "2_2") (pintype "passive"))
      (node (ref "R10") (pin "2") (pinfunction "2_2") (pintype "passive"))
      (node (ref "U1") (pin "2") (pinfunction "XTAL2_/_PC0_2") (pintype "passive"))
      (node (ref "Y1") (pin "2") (pinfunction "2_2") (pintype "passive"))
    )
    (net (code "13") (name "/16U2_BUF_RESETn") (class "Default")
      (node (ref "C29") (pin "2") (pinfunction "2_2") (pintype "passive"))
      (node (ref "R22") (pin "2") (pinfunction "2_2") (pintype "passive"))
      (node (ref "U5") (pin "1") (pinfunction "1_1") (pintype "passive"))
      (node (ref "U5") (pin "2") (pinfunction "2_2") (pintype "passive"))
    )
    (net (code "14") (name "/16U2_HDR_RESETn") (class "Default")
      (node (ref "J6") (pin "5") (pinfunction "5_5") (pintype "passive"))
      (node (ref "JP3") (pin "3") (pinfunction "3_3") (pintype "passive"))
    )
    (net (code "15") (name "/16U2_MISO") (class "Default")
      (node (ref "J6") (pin "1") (pinfunction "1_1") (pintype "passive"))
      (node (ref "U1") (pin "17") (pinfunction "PDO_/_MISO_/_PCINT3_/_PB3_17") (pintype "passive"))
    )
    (net (code "16") (name "/16U2_MOSI") (class "Default")
      (node (ref "J6") (pin "4") (pinfunction "4_4") (pintype "passive"))
      (node (ref "U1") (pin "16") (pinfunction "PDI_/_MOSI_/_PCINT2_/_PB2_16") (pintype "passive"))
    )
    (net (code "17") (name "/16U2_PB4") (class "Default")
      (node (ref "JP2") (pin "1") (pinfunction "1_1") (pintype "passive"))
      (node (ref "JP3") (pin "2") (pinfunction "2_2") (pintype "passive"))
      (node (ref "U1") (pin "18") (pinfunction "T1_/_PCINT4_/_PB4_18") (pintype "passive"))
    )
    (net (code "18") (name "/16U2_PB5") (class "Default")
      (node (ref "JP2") (pin "3") (pinfunction "3_3") (pintype "passive"))
      (node (ref "U1") (pin "19") (pinfunction "PCINT5_/_PB5_19") (pintype "passive"))
    )
    (net (code "19") (name "/16U2_PB6") (class "Default")
      (node (ref "JP2") (pin "2") (pinfunction "2_2") (pintype "passive"))
      (node (ref "U1") (pin "20") (pinfunction "PCINT6_/_PB6_20") (pintype "passive"))
    )
    (net (code "20") (name "/16U2_PB7") (class "Default")
      (node (ref "JP2") (pin "4") (pinfunction "4_4") (pintype "passive"))
      (node (ref "U1") (pin "21") (pinfunction "PCINT7_/_OC.0A_/_OC.1C_/_PB7_21") (pintype "passive"))
    )
    (net (code "21") (name "/16U2_RESETn") (class "Default")
      (node (ref "JP3") (pin "4") (pinfunction "4_4") (pintype "passive"))
      (node (ref "R5") (pin "1") (pinfunction "1_1") (pintype "passive"))
      (node (ref "U1") (pin "24") (pinfunction "PC1_/~{_Reset}_/_DW_24") (pintype "passive"))
      (node (ref "U5") (pin "4") (pinfunction "4_4") (pintype "passive"))
    )
    (net (code "22") (name "/16U2_RXD") (class "Default")
      (node (ref "R12") (pin "1") (pinfunction "1_1") (pintype "passive"))
      (node (ref "U1") (pin "8") (pinfunction "RXD1_/_AIN1_/_INT2_/_PD2_8") (pintype "passive"))
    )
    (net (code "23") (name "/16U2_RX_LED") (class "Default")
      (node (ref "D1") (pin "1") (pinfunction "Cathode_1") (pintype "passive"))
      (node (ref "U1") (pin "10") (pinfunction "INT5_/_AIN3_/_PD4_10") (pintype "passive"))
    )
    (net (code "24") (name "/16U2_SCLK_R") (class "Default")
      (node (ref "J6") (pin "3") (pinfunction "3_3") (pintype "passive"))
      (node (ref "R6") (pin "1") (pinfunction "1_1") (pintype "passive"))
      (node (ref "R6") (pin "2") (pinfunction "2_2") (pintype "passive"))
      (node (ref "U1") (pin "15") (pinfunction "SCLK_/_PCINT1_/_PB1_15") (pintype "passive"))
    )
    (net (code "25") (name "/16U2_TXD") (class "Default")
      (node (ref "R11") (pin "1") (pinfunction "1_1") (pintype "passive"))
      (node (ref "U1") (pin "9") (pinfunction "TXD1_/_INT3_/_PD3_9") (pintype "passive"))
    )
    (net (code "26") (name "/16U2_TX_LED") (class "Default")
      (node (ref "D2") (pin "1") (pinfunction "Cathode_1") (pintype "passive"))
      (node (ref "U1") (pin "11") (pinfunction "XCK_AIN4_/_PCINT12_/_PD5_11") (pintype "passive"))
    )
    (net (code "27") (name "/328P RESETn") (class "Default")
      (node (ref "J1") (pin "3") (pinfunction "3_3") (pintype "passive"))
      (node (ref "J5") (pin "5") (pinfunction "5_5") (pintype "passive"))
    )
    (net (code "28") (name "/328P_16MHZ_XTAL1") (class "Default")
      (node (ref "C27") (pin "2") (pinfunction "2_2") (pintype "passive"))
      (node (ref "R20") (pin "1") (pinfunction "1_1") (pintype "passive"))
      (node (ref "U3") (pin "9") (pinfunction "PB6_/_PCINT6_/_XTAL1_/_TOSC1_9") (pintype "passive"))
      (node (ref "Y2") (pin "1") (pinfunction "1_1") (pintype "passive"))
    )
    (net (code "29") (name "/328P_16MHZ_XTAL2") (class "Default")
      (node (ref "C26") (pin "2") (pinfunction "2_2") (pintype "passive"))
      (node (ref "R20") (pin "2") (pinfunction "2_2") (pintype "passive"))
      (node (ref "U3") (pin "10") (pinfunction "PB7_/_PCINT7_/_XTAL2_/_TOSC2_10") (pintype "passive"))
      (node (ref "Y2") (pin "2") (pinfunction "2_2") (pintype "passive"))
    )
    (net (code "30") (name "/328P_AUTORESETn") (class "Default")
      (node (ref "C11") (pin "1") (pinfunction "1_1") (pintype "passive"))
      (node (ref "R25") (pin "1") (pinfunction "1_1") (pintype "passive"))
      (node (ref "U6") (pin "1") (pinfunction "1_1") (pintype "passive"))
    )
    (net (code "31") (name "/328P_BUF_RESETn") (class "Default")
      (node (ref "C32") (pin "2") (pinfunction "2_2") (pintype "passive"))
      (node (ref "R28") (pin "2") (pinfunction "2_2") (pintype "passive"))
      (node (ref "U6") (pin "2") (pinfunction "2_2") (pintype "passive"))
    )
    (net (code "32") (name "/328P_RESETn") (class "Default")
      (node (ref "JP3") (pin "1") (pinfunction "1_1") (pintype "passive"))
      (node (ref "R19") (pin "1") (pinfunction "1_1") (pintype "passive"))
      (node (ref "U3") (pin "1") (pinfunction "PC6_/_PCINT14_/~{_RESET}_1") (pintype "passive"))
      (node (ref "U6") (pin "4") (pinfunction "4_4") (pintype "passive"))
    )
    (net (code "33") (name "/AD0") (class "Default")
      (node (ref "J2") (pin "1") (pinfunction "1_1") (pintype "passive"))
      (node (ref "U3") (pin "23") (pinfunction "ADC0_/_PCINT8_/_PC0_23") (pintype "passive"))
    )
    (net (code "34") (name "/AD1") (class "Default")
      (node (ref "J2") (pin "2") (pinfunction "2_2") (pintype "passive"))
      (node (ref "U3") (pin "24") (pinfunction "ADC1_/_PCINT9_/_PC1_24") (pintype "passive"))
    )
    (net (code "35") (name "/AD2") (class "Default")
      (node (ref "J2") (pin "3") (pinfunction "3_3") (pintype "passive"))
      (node (ref "U3") (pin "25") (pinfunction "ADC2_/_PCINT10_/_PC2_25") (pintype "passive"))
    )
    (net (code "36") (name "/AD3") (class "Default")
      (node (ref "J2") (pin "4") (pinfunction "4_4") (pintype "passive"))
      (node (ref "U3") (pin "26") (pinfunction "ADC3_/_PCINT11_/_PC3_26") (pintype "passive"))
    )
    (net (code "37") (name "/AD4{slash}SDA") (class "Default")
      (node (ref "J2") (pin "5") (pinfunction "5_5") (pintype "passive"))
      (node (ref "J4") (pin "9") (pinfunction "9_9") (pintype "passive"))
      (node (ref "U3") (pin "27") (pinfunction "ADC4_/_SDA_/_PCINT12_/_PC4_27") (pintype "passive"))
    )
    (net (code "38") (name "/AD5{slash}SCL") (class "Default")
      (node (ref "J2") (pin "6") (pinfunction "6_6") (pintype "passive"))
      (node (ref "J4") (pin "10") (pinfunction "10_10") (pintype "passive"))
      (node (ref "U3") (pin "28") (pinfunction "ADC5_/_SCL_/_PCINT13_/_PC5_28") (pintype "passive"))
    )
    (net (code "39") (name "/BUTTON_RESETn") (class "Default")
      (node (ref "D6") (pin "2") (pinfunction "Anode_2") (pintype "passive"))
      (node (ref "R23") (pin "1") (pinfunction "1_1") (pintype "passive"))
      (node (ref "R28") (pin "1") (pinfunction "1_1") (pintype "passive"))
      (node (ref "SW1") (pin "1") (pinfunction "1_1") (pintype "passive"))
      (node (ref "SW1") (pin "2") (pinfunction "2_2") (pintype "passive"))
    )
    (net (code "40") (name "/CON_USB_N") (class "Default")
      (node (ref "J7") (pin "2") (pinfunction "2_2") (pintype "passive"))
      (node (ref "R7") (pin "1") (pinfunction "1_1") (pintype "passive"))
      (node (ref "Z1") (pin "2") (pinfunction "2_2") (pintype "passive"))
    )
    (net (code "41") (name "/CON_USB_P") (class "Default")
      (node (ref "J7") (pin "3") (pinfunction "3_3") (pintype "passive"))
      (node (ref "R8") (pin "1") (pinfunction "1_1") (pintype "passive"))
      (node (ref "Z2") (pin "2") (pinfunction "2_2") (pintype "passive"))
    )
    (net (code "42") (name "/IO0") (class "Default")
      (node (ref "J3") (pin "1") (pinfunction "1_1") (pintype "passive"))
      (node (ref "R11") (pin "2") (pinfunction "2_2") (pintype "passive"))
      (node (ref "U3") (pin "2") (pinfunction "PCINT16_/_RXD_/_PD0_2") (pintype "passive"))
    )
    (net (code "43") (name "/IO1") (class "Default")
      (node (ref "J3") (pin "2") (pinfunction "2_2") (pintype "passive"))
      (node (ref "R12") (pin "2") (pinfunction "2_2") (pintype "passive"))
      (node (ref "U3") (pin "3") (pinfunction "PCINT17_/_TXD_/_PD1_3") (pintype "passive"))
    )
    (net (code "44") (name "/IO2") (class "Default")
      (node (ref "J3") (pin "3") (pinfunction "3_3") (pintype "passive"))
      (node (ref "U3") (pin "4") (pinfunction "PCINT18_/_INT0_/_PD2_4") (pintype "passive"))
    )
    (net (code "45") (name "/IO3") (class "Default")
      (node (ref "J3") (pin "4") (pinfunction "4_4") (pintype "passive"))
      (node (ref "U3") (pin "5") (pinfunction "PCINT19_/_OC2B_/_INT1_/_PD3_5") (pintype "passive"))
    )
    (net (code "46") (name "/IO4") (class "Default")
      (node (ref "J3") (pin "5") (pinfunction "5_5") (pintype "passive"))
      (node (ref "U3") (pin "6") (pinfunction "PCINT20_/_XCK_/_T0_/_PD4_6") (pintype "passive"))
    )
    (net (code "47") (name "/IO5") (class "Default")
      (node (ref "J3") (pin "6") (pinfunction "6_6") (pintype "passive"))
      (node (ref "U3") (pin "11") (pinfunction "PCINT21_/_OC0B_/_T1_/_PD5_11") (pintype "passive"))
    )
    (net (code "48") (name "/IO6") (class "Default")
      (node (ref "J3") (pin "7") (pinfunction "7_7") (pintype "passive"))
      (node (ref "U3") (pin "12") (pinfunction "PCINT22_/_OC0A_/_AIN0_/_PD6_12") (pintype "passive"))
    )
    (net (code "49") (name "/IO7") (class "Default")
      (node (ref "J3") (pin "8") (pinfunction "8_8") (pintype "passive"))
      (node (ref "U3") (pin "13") (pinfunction "PCINT23_/_AIN1_/_PD7_13") (pintype "passive"))
    )
    (net (code "50") (name "/IO8") (class "Default")
      (node (ref "J4") (pin "1") (pinfunction "1_1") (pintype "passive"))
      (node (ref "R26") (pin "2") (pinfunction "2_2") (pintype "passive"))
      (node (ref "U3") (pin "14") (pinfunction "PCINT0_/_CLKO_/_ICP1_/_PB0_14") (pintype "passive"))
    )
    (net (code "51") (name "/IO9") (class "Default")
      (node (ref "J4") (pin "2") (pinfunction "2_2") (pintype "passive"))
      (node (ref "U3") (pin "15") (pinfunction "OC1A_/_PCINT1_/_PB1_15") (pintype "passive"))
    )
    (net (code "52") (name "/MISO") (class "Default")
      (node (ref "J4") (pin "5") (pinfunction "5_5") (pintype "passive"))
      (node (ref "J5") (pin "1") (pinfunction "1_1") (pintype "passive"))
      (node (ref "U3") (pin "18") (pinfunction "MISO_/_PCINT4_/_PB4_18") (pintype "passive"))
    )
    (net (code "53") (name "/MOSI") (class "Default")
      (node (ref "J4") (pin "4") (pinfunction "4_4") (pintype "passive"))
      (node (ref "J5") (pin "4") (pinfunction "4_4") (pintype "passive"))
      (node (ref "U3") (pin "17") (pinfunction "MOSI_/_OC2A_/_PCINT3_/_PB3_17") (pintype "passive"))
    )
    (net (code "54") (name "/SCK") (class "Default")
      (node (ref "J4") (pin "6") (pinfunction "6_6") (pintype "passive"))
      (node (ref "J5") (pin "3") (pinfunction "3_3") (pintype "passive"))
      (node (ref "R16") (pin "2") (pinfunction "2_2") (pintype "passive"))
      (node (ref "U4") (pin "1") (pinfunction "1_1") (pintype "passive"))
      (node (ref "U4") (pin "2") (pinfunction "2_2") (pintype "passive"))
    )
    (net (code "55") (name "/SCK_R") (class "Default")
      (node (ref "R16") (pin "1") (pinfunction "1_1") (pintype "passive"))
      (node (ref "U3") (pin "19") (pinfunction "SCK_/_PCINT5_/_PB5_19") (pintype "passive"))
    )
    (net (code "56") (name "/SS") (class "Default")
      (node (ref "J4") (pin "3") (pinfunction "3_3") (pintype "passive"))
      (node (ref "U3") (pin "16") (pinfunction "~{SS}_/_OC1B_/_PCINT2_/_PB2_16") (pintype "passive"))
    )
    (net (code "57") (name "/USB_N") (class "Default")
      (node (ref "R7") (pin "2") (pinfunction "2_2") (pintype "passive"))
      (node (ref "U1") (pin "30") (pinfunction "D-_30") (pintype "passive"))
    )
    (net (code "58") (name "/USB_P") (class "Default")
      (node (ref "R8") (pin "2") (pinfunction "2_2") (pintype "passive"))
      (node (ref "U1") (pin "29") (pinfunction "D+_29") (pintype "passive"))
    )
    (net (code "59") (name "/USER_BUTTON") (class "Default")
      (node (ref "R24") (pin "1") (pinfunction "1_1") (pintype "passive"))
      (node (ref "R27") (pin "1") (pinfunction "1_1") (pintype "passive"))
      (node (ref "SW2") (pin "1") (pinfunction "1_1") (pintype "passive"))
      (node (ref "SW2") (pin "2") (pinfunction "2_2") (pintype "passive"))
    )
    (net (code "60") (name "/USER_BUTTON_BUF") (class "Default")
      (node (ref "C33") (pin "2") (pinfunction "2_2") (pintype "passive"))
      (node (ref "R27") (pin "2") (pinfunction "2_2") (pintype "passive"))
      (node (ref "U7") (pin "1") (pinfunction "1_1") (pintype "passive"))
      (node (ref "U7") (pin "2") (pinfunction "2_2") (pintype "passive"))
    )
    (net (code "61") (name "GND") (class "Default")
      (node (ref "C1") (pin "1") (pinfunction "1_1") (pintype "passive"))
      (node (ref "C10") (pin "1") (pinfunction "1_1") (pintype "passive"))
      (node (ref "C12") (pin "1") (pinfunction "1_1") (pintype "passive"))
      (node (ref "C13") (pin "1") (pinfunction "1_1") (pintype "passive"))
      (node (ref "C14") (pin "1") (pinfunction "1_1") (pintype "passive"))
      (node (ref "C15") (pin "1") (pinfunction "1_1") (pintype "passive"))
      (node (ref "C16") (pin "1") (pinfunction "1_1") (pintype "passive"))
      (node (ref "C17") (pin "1") (pinfunction "1_1") (pintype "passive"))
      (node (ref "C18") (pin "1") (pinfunction "1_1") (pintype "passive"))
      (node (ref "C19") (pin "1") (pinfunction "1_1") (pintype "passive"))
      (node (ref "C2") (pin "1") (pinfunction "1_1") (pintype "passive"))
      (node (ref "C20") (pin "1") (pinfunction "1_1") (pintype "passive"))
      (node (ref "C21") (pin "1") (pinfunction "1_1") (pintype "passive"))
      (node (ref "C22") (pin "1") (pinfunction "1_1") (pintype "passive"))
      (node (ref "C23") (pin "1") (pinfunction "1_1") (pintype "passive"))
      (node (ref "C24") (pin "1") (pinfunction "1_1") (pintype "passive"))
      (node (ref "C25") (pin "1") (pinfunction "1_1") (pintype "passive"))
      (node (ref "C26") (pin "1") (pinfunction "1_1") (pintype "passive"))
      (node (ref "C27") (pin "1") (pinfunction "1_1") (pintype "passive"))
      (node (ref "C28") (pin "1") (pinfunction "1_1") (pintype "passive"))
      (node (ref "C29") (pin "1") (pinfunction "1_1") (pintype "passive"))
      (node (ref "C3") (pin "1") (pinfunction "1_1") (pintype "passive"))
      (node (ref "C30") (pin "1") (pinfunction "1_1") (pintype "passive"))
      (node (ref "C31") (pin "1") (pinfunction "1_1") (pintype "passive"))
      (node (ref "C32") (pin "1") (pinfunction "1_1") (pintype "passive"))
      (node (ref "C33") (pin "1") (pinfunction "1_1") (pintype "passive"))
      (node (ref "C4") (pin "1") (pinfunction "1_1") (pintype "passive"))
      (node (ref "C5") (pin "2") (pinfunction "2_2") (pintype "passive"))
      (node (ref "C6") (pin "2") (pinfunction "2_2") (pintype "passive"))
      (node (ref "C7") (pin "1") (pinfunction "1_1") (pintype "passive"))
      (node (ref "C8") (pin "1") (pinfunction "1_1") (pintype "passive"))
      (node (ref "C9") (pin "1") (pinfunction "1_1") (pintype "passive"))
      (node (ref "D4") (pin "1") (pinfunction "Cathode_1") (pintype "passive"))
      (node (ref "J1") (pin "6") (pinfunction "6_6") (pintype "passive"))
      (node (ref "J1") (pin "7") (pinfunction "7_7") (pintype "passive"))
      (node (ref "J4") (pin "7") (pinfunction "7_7") (pintype "passive"))
      (node (ref "J5") (pin "6") (pinfunction "6_6") (pintype "passive"))
      (node (ref "J6") (pin "6") (pinfunction "6_6") (pintype "passive"))
      (node (ref "J7") (pin "10") (pinfunction "10_10") (pintype "passive"))
      (node (ref "J7") (pin "11") (pinfunction "11_11") (pintype "passive"))
      (node (ref "J7") (pin "5") (pinfunction "5_5") (pintype "passive"))
      (node (ref "J7") (pin "6") (pinfunction "6_6") (pintype "passive"))
      (node (ref "J7") (pin "7") (pinfunction "7_7") (pintype "passive"))
      (node (ref "J7") (pin "8") (pinfunction "8_8") (pintype "passive"))
      (node (ref "J7") (pin "9") (pinfunction "9_9") (pintype "passive"))
      (node (ref "J9") (pin "1") (pinfunction "1_1") (pintype "passive"))
      (node (ref "MH1") (pin "1") (pinfunction "1_1") (pintype "passive"))
      (node (ref "MH2") (pin "1") (pinfunction "1_1") (pintype "passive"))
      (node (ref "MH3") (pin "1") (pinfunction "1_1") (pintype "passive"))
      (node (ref "R13") (pin "1") (pinfunction "1_1") (pintype "passive"))
      (node (ref "R9") (pin "2") (pinfunction "2_2") (pintype "passive"))
      (node (ref "SW1") (pin "3") (pinfunction "3_3") (pintype "passive"))
      (node (ref "SW1") (pin "4") (pinfunction "4_4") (pintype "passive"))
      (node (ref "SW2") (pin "3") (pinfunction "3_3") (pintype "passive"))
      (node (ref "SW2") (pin "4") (pinfunction "4_4") (pintype "passive"))
      (node (ref "U1") (pin "28") (pinfunction "UGND_28") (pintype "passive"))
      (node (ref "U1") (pin "3") (pinfunction "GND_3") (pintype "passive"))
      (node (ref "U2") (pin "3") (pinfunction "GND_3") (pintype "passive"))
      (node (ref "U2") (pin "6") (pinfunction "EPAD_6") (pintype "passive"))
      (node (ref "U3") (pin "22") (pinfunction "GND_2_22") (pintype "passive"))
      (node (ref "U3") (pin "8") (pinfunction "GND_1_8") (pintype "passive"))
      (node (ref "U4") (pin "3") (pinfunction "3_3") (pintype "passive"))
      (node (ref "U5") (pin "3") (pinfunction "3_3") (pintype "passive"))
      (node (ref "U6") (pin "3") (pinfunction "3_3") (pintype "passive"))
      (node (ref "U7") (pin "3") (pinfunction "3_3") (pintype "passive"))
      (node (ref "Z1") (pin "1") (pinfunction "1_1") (pintype "passive"))
      (node (ref "Z2") (pin "1") (pinfunction "1_1") (pintype "passive"))
    )
    (net (code "62") (name "Net-(C11-Pad2)") (class "Default")
      (node (ref "C11") (pin "2") (pinfunction "2_2") (pintype "passive"))
      (node (ref "JP1") (pin "1") (pinfunction "1_1") (pintype "passive"))
    )
    (net (code "63") (name "Net-(D1-Anode)") (class "Default")
      (node (ref "D1") (pin "2") (pinfunction "Anode_2") (pintype "passive"))
      (node (ref "R1") (pin "1") (pinfunction "1_1") (pintype "passive"))
    )
    (net (code "64") (name "Net-(D2-Anode)") (class "Default")
      (node (ref "D2") (pin "2") (pinfunction "Anode_2") (pintype "passive"))
      (node (ref "R2") (pin "1") (pinfunction "1_1") (pintype "passive"))
    )
    (net (code "65") (name "Net-(D3-Anode)") (class "Default")
      (node (ref "D3") (pin "2") (pinfunction "Anode_2") (pintype "passive"))
      (node (ref "R17") (pin "1") (pinfunction "1_1") (pintype "passive"))
    )
    (net (code "66") (name "Net-(D3-Cathode)") (class "Default")
      (node (ref "D3") (pin "1") (pinfunction "Cathode_1") (pintype "passive"))
      (node (ref "U4") (pin "4") (pinfunction "4_4") (pintype "passive"))
    )
    (net (code "67") (name "Net-(D4-Anode)") (class "Default")
      (node (ref "D4") (pin "2") (pinfunction "Anode_2") (pintype "passive"))
      (node (ref "R18") (pin "1") (pinfunction "1_1") (pintype "passive"))
    )
    (net (code "68") (name "Net-(D5-Anode)") (class "Default")
      (node (ref "D5") (pin "2") (pinfunction "Anode_2") (pintype "passive"))
      (node (ref "R21") (pin "1") (pinfunction "1_1") (pintype "passive"))
      (node (ref "R22") (pin "1") (pinfunction "1_1") (pintype "passive"))
    )
    (net (code "69") (name "Net-(J7-Pad4)") (class "Default")
      (node (ref "J7") (pin "4") (pinfunction "4_4") (pintype "passive"))
      (node (ref "R9") (pin "1") (pinfunction "1_1") (pintype "passive"))
    )
    (net (code "70") (name "Net-(JP1-Pad3)") (class "Default")
      (node (ref "JP1") (pin "3") (pinfunction "3_3") (pintype "passive"))
      (node (ref "R13") (pin "2") (pinfunction "2_2") (pintype "passive"))
    )
    (net (code "71") (name "Net-(R26-Pad1)") (class "Default")
      (node (ref "R26") (pin "1") (pinfunction "1_1") (pintype "passive"))
      (node (ref "U7") (pin "4") (pinfunction "4_4") (pintype "passive"))
    )
    (net (code "72") (name "unconnected-(J1-Pad1)") (class "Default")
      (node (ref "J1") (pin "1") (pinfunction "1_1") (pintype "passive+no_connect"))
    )
    (net (code "73") (name "unconnected-(J1-Pad8)") (class "Default")
      (node (ref "J1") (pin "8") (pinfunction "8_8") (pintype "passive+no_connect"))
    )
    (net (code "74") (name "unconnected-(MH4-Pad1)") (class "Default")
      (node (ref "MH4") (pin "1") (pinfunction "1_1") (pintype "passive+no_connect"))
    )
    (net (code "75") (name "unconnected-(U1-AIN0_{slash}_INT1_{slash}_PD1-Pad7)") (class "Default")
      (node (ref "U1") (pin "7") (pinfunction "AIN0_/_INT1_/_PD1_7") (pintype "passive+no_connect"))
    )
    (net (code "76") (name "unconnected-(U1-INT4_{slash}_ICP1_{slash}_CLKO_{slash}_PC7-Pad22)") (class "Default")
      (node (ref "U1") (pin "22") (pinfunction "INT4_/_ICP1_/_CLKO_/_PC7_22") (pintype "passive+no_connect"))
    )
    (net (code "77") (name "unconnected-(U1-OC.0B_{slash}_INT0_{slash}_PD0-Pad6)") (class "Default")
      (node (ref "U1") (pin "6") (pinfunction "OC.0B_/_INT0_/_PD0_6") (pintype "passive+no_connect"))
    )
    (net (code "78") (name "unconnected-(U1-OC.1A_{slash}_PCINT8_{slash}_PC6-Pad23)") (class "Default")
      (node (ref "U1") (pin "23") (pinfunction "OC.1A_/_PCINT8_/_PC6_23") (pintype "passive+no_connect"))
    )
    (net (code "79") (name "unconnected-(U1-PCINT9{slash}_OC.1B_{slash}_PC5-Pad25)") (class "Default")
      (node (ref "U1") (pin "25") (pinfunction "PCINT9/_OC.1B_/_PC5_25") (pintype "passive+no_connect"))
    )
    (net (code "80") (name "unconnected-(U1-PCINT10_{slash}_PC4-Pad26)") (class "Default")
      (node (ref "U1") (pin "26") (pinfunction "PCINT10_/_PC4_26") (pintype "passive+no_connect"))
    )
    (net (code "81") (name "unconnected-(U1-PCINT11_{slash}AIN2_{slash}_PC2-Pad5)") (class "Default")
      (node (ref "U1") (pin "5") (pinfunction "PCINT11_/AIN2_/_PC2_5") (pintype "passive+no_connect"))
    )
    (net (code "82") (name "unconnected-(U1-~{RTS}_{slash}_AIN5_{slash}_INT6_{slash}_PD6-Pad12)") (class "Default")
      (node (ref "U1") (pin "12") (pinfunction "~{RTS}_/_AIN5_/_INT6_/_PD6_12") (pintype "passive+no_connect"))
    )
    (net (code "83") (name "unconnected-(U1-~{SS}_{slash}_PCINT0_{slash}_PB0-Pad14)") (class "Default")
      (node (ref "U1") (pin "14") (pinfunction "~{SS}_/_PCINT0_/_PB0_14") (pintype "passive+no_connect"))
    )
  )
)
